# PWR_Supply.net
KiCad netlist of a schematic drawn in Altium Designer
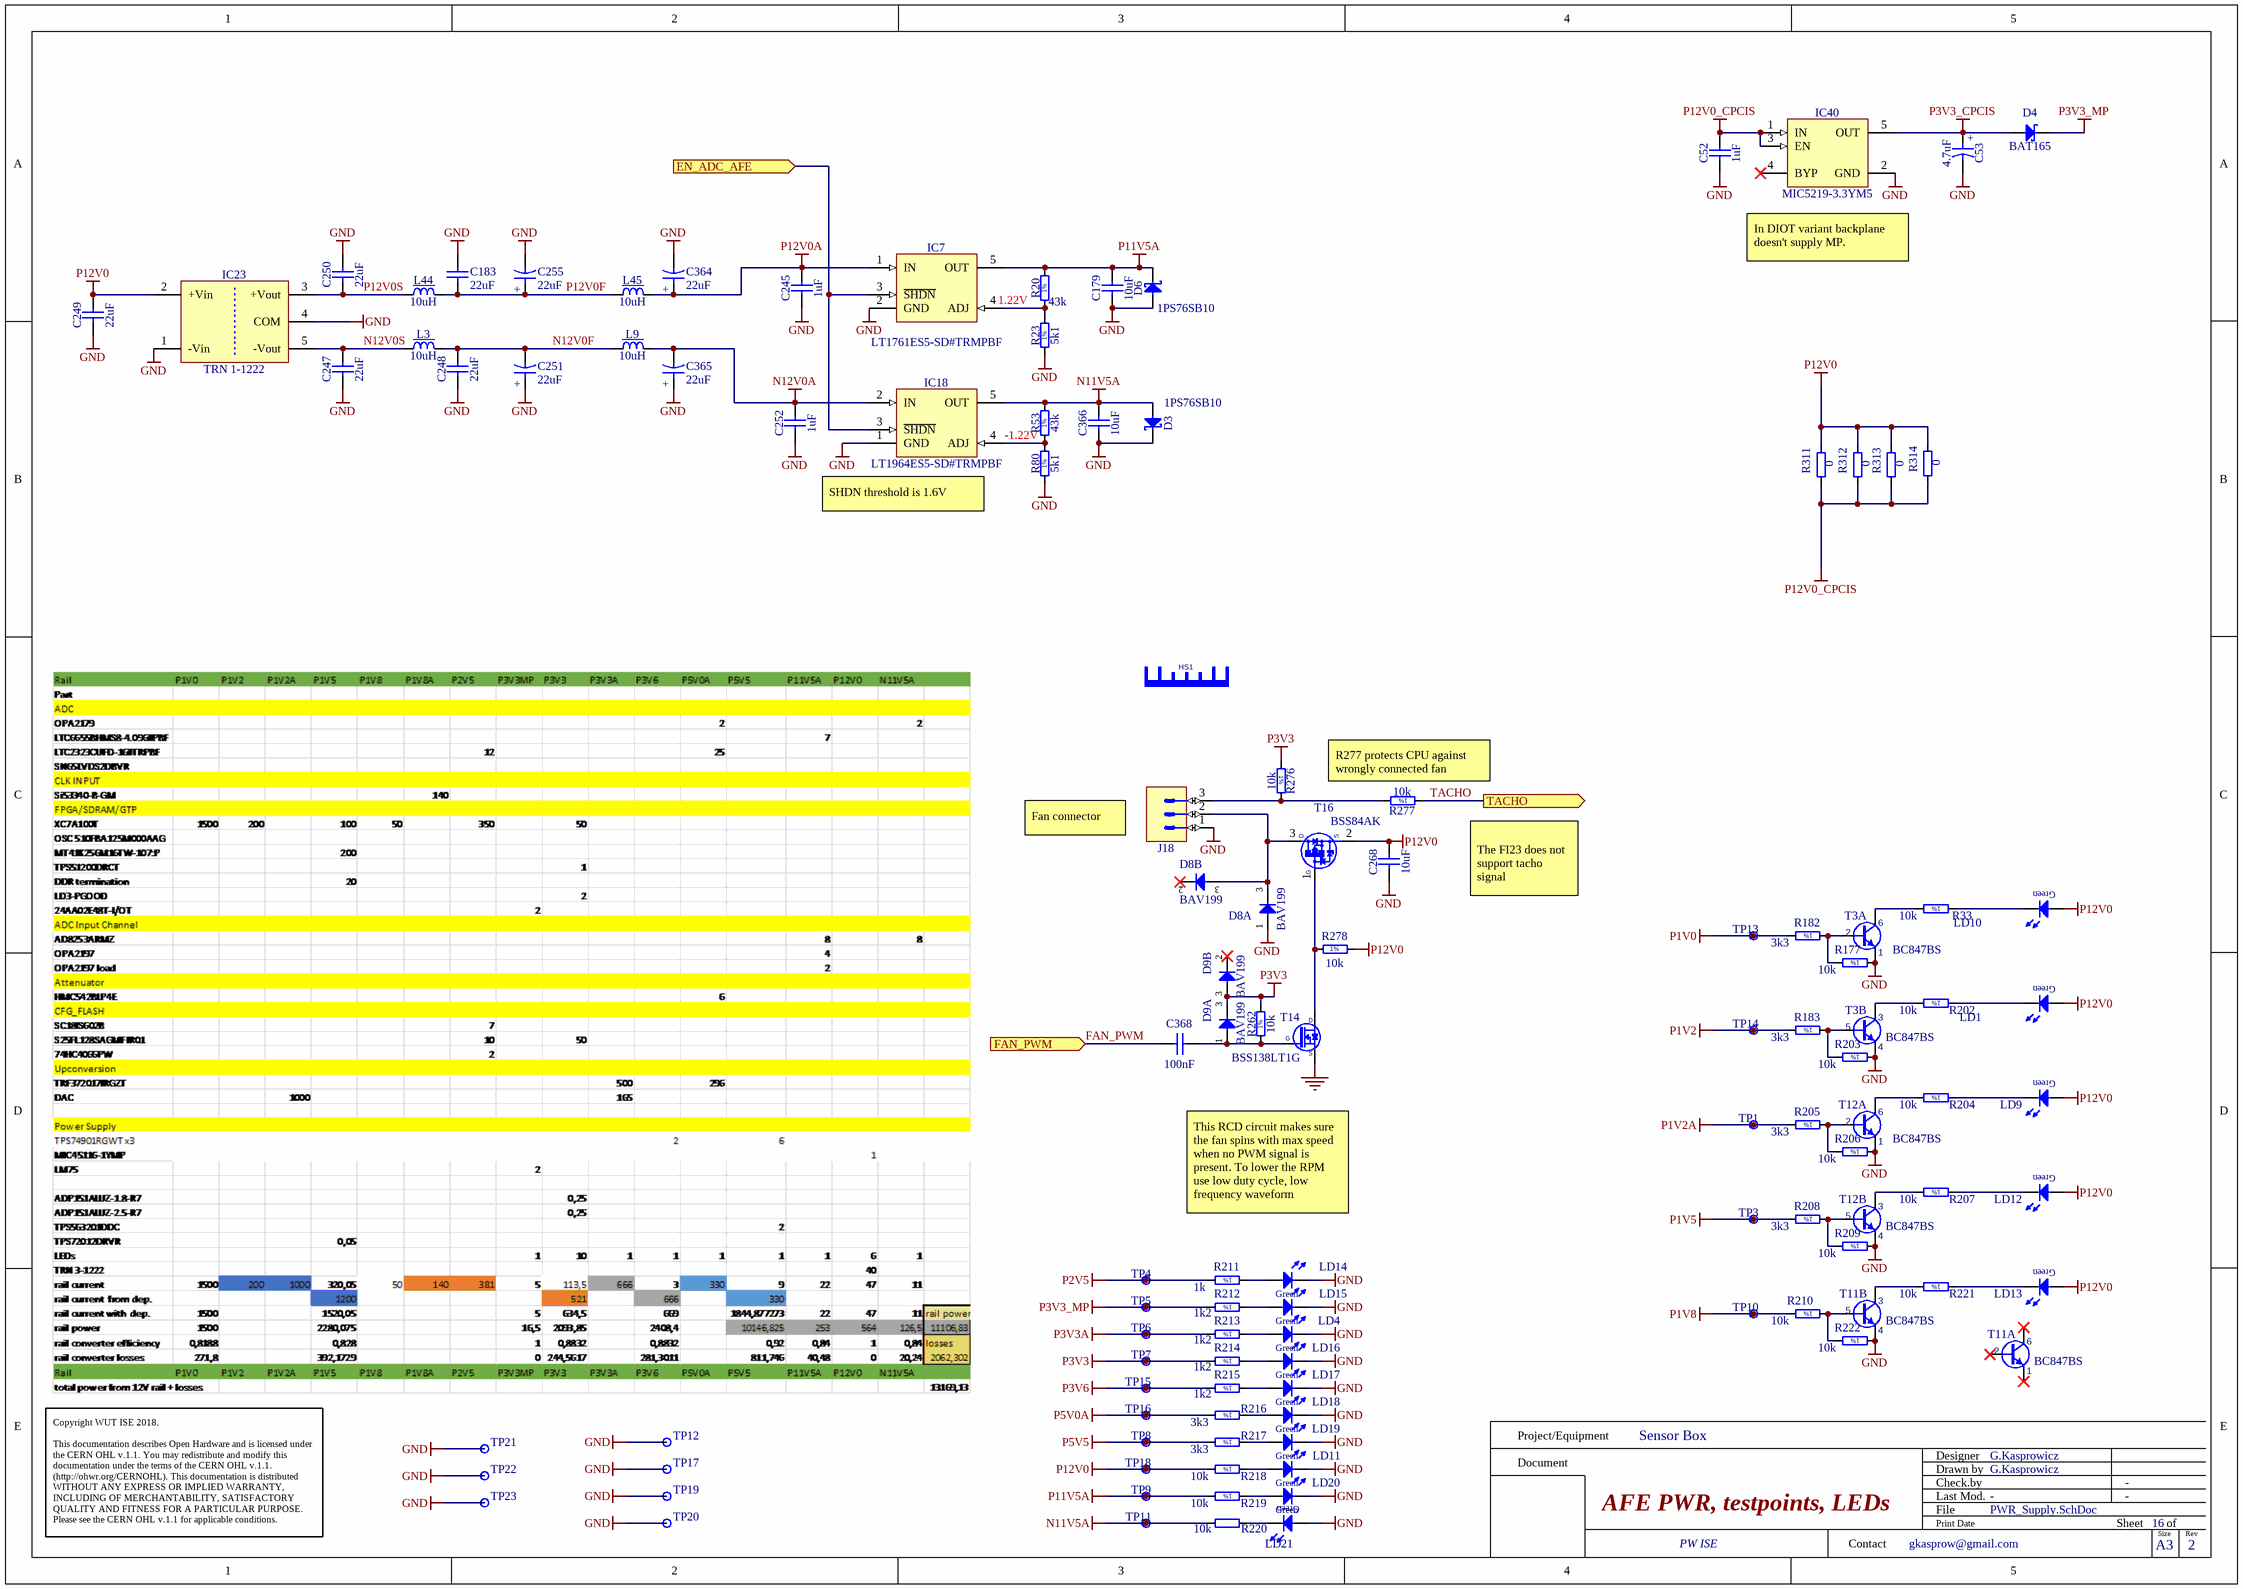
[diagram p0: PWR_Supply.SchDoc]

(export (version "E")
  (design (tool "Eeschema 10.0.6"))
  (components
    (comp (ref "C52")
      (value "1uF")
      (footprint "CAPC1608X87N")
      (description "Non-polarised capacitor")
      (fields (field (name "PART NUMBER") "CC0603_1UF_25V_10%_X7R") (field (name "VOLTAGE") "25V"))
      (libsource (lib "Capacitors") (part "Capacitor - non polarized"))
    )
    (comp (ref "C53")
      (value "4.7uF")
      (footprint "CAPMP3216X180N")
      (description "Polarised capacitor")
      (fields
        (field (name "PART NUMBER") "CTE3216-18_4.7UF_10V_10%_AVX_TPSA475K010T1400")
        (field (name "VOLTAGE") "10V")
      )
      (libsource (lib "Capacitors") (part "Capacitor - polarized"))
    )
    (comp (ref "C179")
      (value "10uF")
      (footprint "CAPC2012X135N")
      (description "Non-polarised capacitor")
      (fields (field (name "PART NUMBER") "CC0805_10UF_16V_10%_X5R") (field (name "VOLTAGE") "16V"))
      (libsource (lib "Capacitors") (part "Capacitor - non polarized"))
    )
    (comp (ref "C183")
      (value "22uF")
      (footprint "CAPC2012X135N")
      (description "Non-polarised capacitor")
      (fields (field (name "PART NUMBER") "CC0805_22UF_16V_10%_X5R") (field (name "VOLTAGE") "16V"))
      (libsource (lib "Capacitors") (part "Capacitor - non polarized"))
    )
    (comp (ref "C245")
      (value "1uF")
      (footprint "CAPC1608X87N")
      (description "Non-polarised capacitor")
      (fields (field (name "PART NUMBER") "CC0603_1UF_25V_10%_X7R") (field (name "VOLTAGE") "25V"))
      (libsource (lib "Capacitors") (part "Capacitor - non polarized"))
    )
    (comp (ref "C247")
      (value "22uF")
      (footprint "CAPC2012X135N")
      (description "Non-polarised capacitor")
      (fields (field (name "PART NUMBER") "CC0805_22UF_16V_10%_X5R") (field (name "VOLTAGE") "16V"))
      (libsource (lib "Capacitors") (part "Capacitor - non polarized"))
    )
    (comp (ref "C248")
      (value "22uF")
      (footprint "CAPC2012X135N")
      (description "Non-polarised capacitor")
      (fields (field (name "PART NUMBER") "CC0805_22UF_16V_10%_X5R") (field (name "VOLTAGE") "16V"))
      (libsource (lib "Capacitors") (part "Capacitor - non polarized"))
    )
    (comp (ref "C249")
      (value "22uF")
      (footprint "CAPC2012X135N")
      (description "Non-polarised capacitor")
      (fields (field (name "PART NUMBER") "CC0805_22UF_16V_10%_X5R") (field (name "VOLTAGE") "16V"))
      (libsource (lib "Capacitors") (part "Capacitor - non polarized"))
    )
    (comp (ref "C250")
      (value "22uF")
      (footprint "CAPC2012X135N")
      (description "Non-polarised capacitor")
      (fields (field (name "PART NUMBER") "CC0805_22UF_16V_10%_X5R") (field (name "VOLTAGE") "16V"))
      (libsource (lib "Capacitors") (part "Capacitor - non polarized"))
    )
    (comp (ref "C251")
      (value "22uF")
      (footprint "CAPMP3528X210N")
      (description "Polarised capacitor")
      (fields (field (name "PART NUMBER") "CTE3528-21_22UF_10V_10%_LESR0700") (field (name "VOLTAGE") "10V"))
      (libsource (lib "Capacitors") (part "Capacitor - polarized"))
    )
    (comp (ref "C252")
      (value "1uF")
      (footprint "CAPC1608X87N")
      (description "Non-polarised capacitor")
      (fields (field (name "PART NUMBER") "CC0603_1UF_25V_10%_X7R") (field (name "VOLTAGE") "25V"))
      (libsource (lib "Capacitors") (part "Capacitor - non polarized"))
    )
    (comp (ref "C255")
      (value "22uF")
      (footprint "CAPMP3528X210N")
      (description "Polarised capacitor")
      (fields (field (name "PART NUMBER") "CTE3528-21_22UF_10V_10%_LESR0700") (field (name "VOLTAGE") "10V"))
      (libsource (lib "Capacitors") (part "Capacitor - polarized"))
    )
    (comp (ref "C268")
      (value "10uF")
      (footprint "CAPC2012X135N")
      (description "Non-polarised capacitor")
      (fields (field (name "PART NUMBER") "CC0805_10UF_16V_10%_X5R") (field (name "VOLTAGE") "16V"))
      (libsource (lib "Capacitors") (part "Capacitor - non polarized"))
    )
    (comp (ref "C364")
      (value "22uF")
      (footprint "CAPMP3528X210N")
      (description "Polarised capacitor")
      (fields (field (name "PART NUMBER") "CTE3528-21_22UF_10V_10%_LESR0700") (field (name "VOLTAGE") "10V"))
      (libsource (lib "Capacitors") (part "Capacitor - polarized"))
    )
    (comp (ref "C365")
      (value "22uF")
      (footprint "CAPMP3528X210N")
      (description "Polarised capacitor")
      (fields (field (name "PART NUMBER") "CTE3528-21_22UF_10V_10%_LESR0700") (field (name "VOLTAGE") "10V"))
      (libsource (lib "Capacitors") (part "Capacitor - polarized"))
    )
    (comp (ref "C366")
      (value "10uF")
      (footprint "CAPC2012X135N")
      (description "Non-polarised capacitor")
      (fields (field (name "PART NUMBER") "CC0805_10UF_16V_10%_X5R") (field (name "VOLTAGE") "16V"))
      (libsource (lib "Capacitors") (part "Capacitor - non polarized"))
    )
    (comp (ref "C368")
      (value "100nF")
      (footprint "CAPC0603X33N")
      (description "Non-polarised capacitor")
      (fields (field (name "PART NUMBER") "CC0201_100NF_6.3V_10%_X5R") (field (name "VOLTAGE") "6.3V"))
      (libsource (lib "Capacitors") (part "Capacitor - non polarized"))
    )
    (comp (ref "D3")
      (value "1PS76SB10")
      (footprint "SOD2512X110N")
      (description "Schottky Diode")
      (fields (field (name "VOLTAGE") "30V") (field (name "POWER") "200mA"))
      (libsource (lib "ICs And Semiconductors") (part "Diode Schottky"))
    )
    (comp (ref "D4")
      (value "BAT165")
      (footprint "SOD2512X110N")
      (description "Schottky Diode")
      (fields (field (name "MANUFACTURER") "INFINEON") (field (name "VOLTAGE") "40V"))
      (libsource (lib "ICs And Semiconductors") (part "Diode Schottky"))
    )
    (comp (ref "D6")
      (value "1PS76SB10")
      (footprint "SOD2512X110N")
      (description "Schottky Diode")
      (fields (field (name "VOLTAGE") "30V") (field (name "POWER") "200mA"))
      (libsource (lib "ICs And Semiconductors") (part "Diode Schottky"))
    )
    (comp (ref "D8")
      (value "BAV199")
      (footprint "SOT95P240X110-3N")
      (description "Serial Diode")
      (fields (field (name "VOLTAGE") "75V") (field (name "POWER") "250mW"))
      (libsource (lib "ICs And Semiconductors") (part "Diode x2 A1C3_A3C2"))
    )
    (comp (ref "D9")
      (value "BAV199")
      (footprint "SOT95P240X110-3N")
      (description "Serial Diode")
      (fields (field (name "VOLTAGE") "75V") (field (name "POWER") "250mW"))
      (libsource (lib "ICs And Semiconductors") (part "Diode x2 A1C3_A3C2"))
    )
    (comp (ref "HS1")
      (value "RADIAN_FI23")
      (footprint "RADIAN_FI23")
      (description "Heat Sink Without Pad")
      (fields
        (field (name "MANUFACTURER") "Radian Thermal Products, Inc.")
        (field (name "MANUFACTURER PART NUMBER") "FI23+BU+T725")
      )
      (libsource (lib "Schlib1") (part "RADIAN_FI23"))
    )
    (comp (ref "IC7")
      (value "LT1761ES5-SD#TRMPBF")
      (footprint "SOT95P280X100-5N")
      (description "100mA, Low Noise, LDO Micropower Adjustable Regulator in SOT-23")
      (fields (field (name "MANUFACTURER") "LINEAR TECHNOLOGY"))
      (libsource (lib "ICs And Semiconductors") (part "LT1761-SD"))
    )
    (comp (ref "IC18")
      (value "LT1964ES5-SD#TRMPBF")
      (footprint "SOT95P280X100-5N")
      (description "200mA, Low Noise, Low Dropout Negative Micropower Regulator")
      (fields (field (name "MANUFACTURER") "LINEAR TECHNOLOGY"))
      (libsource (lib "ICs And Semiconductors") (part "LT1964-SD"))
    )
    (comp (ref "IC23")
      (value "TRN 1-1222")
      (footprint "DCDC_TRACO_TRN1")
      (description "9-18VDC to ±12V, Iout (max) ±45mA, 1W DC-DC Converter")
      (fields (field (name "MANUFACTURER") "TRACO POWER"))
      (libsource (lib "Regulators_SMPS") (part "DCDC_TRACO_TRN 1-1222"))
    )
    (comp (ref "IC40")
      (value "MIC5219-3.3YM5")
      (footprint "SOT95P280X145-5N")
      (description "500mA Peak Output LDO Regulator")
      (fields (field (name "MANUFACTURER") "MICROCHIP TECHNOLOGY"))
      (libsource (lib "ICs And Semiconductors") (part "MIC5219-X.XYM5"))
    )
    (comp (ref "J18")
      (value "KK®")
      (footprint "MOLEX_22-27-2031")
      (description "Connector 3 Male")
      (fields (field (name "PART NUMBER") "MOLEX_22-27-2031") (field (name "MANUFACTURER") "MOLEX"))
      (libsource (lib "Connectors") (part "Connector 3 Male"))
    )
    (comp (ref "L3")
      (value "10uH")
      (footprint "IND_MURATA-PS_8400")
      (description "Inductor With Core")
      (fields (field (name "PART NUMBER") "IND_10UH_10%_MURATA-PS_8400") (field (name "POWER") "950mA"))
      (libsource (lib "Inductors & Transformers") (part "Inductor With Magnetic core"))
    )
    (comp (ref "L9")
      (value "10uH")
      (footprint "IND_MURATA-PS_8400")
      (description "Inductor With Core")
      (fields (field (name "PART NUMBER") "IND_10UH_10%_MURATA-PS_8400") (field (name "POWER") "950mA"))
      (libsource (lib "Inductors & Transformers") (part "Inductor With Magnetic core"))
    )
    (comp (ref "L44")
      (value "10uH")
      (footprint "IND_MURATA-PS_8400")
      (description "Inductor With Core")
      (fields (field (name "PART NUMBER") "IND_10UH_10%_MURATA-PS_8400") (field (name "POWER") "950mA"))
      (libsource (lib "Inductors & Transformers") (part "Inductor With Magnetic core"))
    )
    (comp (ref "L45")
      (value "10uH")
      (footprint "IND_MURATA-PS_8400")
      (description "Inductor With Core")
      (fields (field (name "PART NUMBER") "IND_10UH_10%_MURATA-PS_8400") (field (name "POWER") "950mA"))
      (libsource (lib "Inductors & Transformers") (part "Inductor With Magnetic core"))
    )
    (comp (ref "LD1")
      (value "Green")
      (footprint "LED_KINGBRIGHT_KPH-1608CGCKr")
      (description "Green 0603")
      (fields
        (field (name "PART NUMBER") "LED_KINGBRIGHT_KPH-1608CGCK")
        (field (name "MANUFACTURER") "KINGBRIGHT")
      )
      (libsource (lib "LIBRARY_SCH") (part "LED_0603_Green"))
    )
    (comp (ref "LD4")
      (value "Green")
      (footprint "LED_KINGBRIGHT_KPH-1608CGCKr")
      (description "Green 0603")
      (fields
        (field (name "PART NUMBER") "LED_KINGBRIGHT_KPH-1608CGCK")
        (field (name "MANUFACTURER") "KINGBRIGHT")
      )
      (libsource (lib "LIBRARY_SCH") (part "LED_0603_Green"))
    )
    (comp (ref "LD9")
      (value "Green")
      (footprint "LED_KINGBRIGHT_KPH-1608CGCKr")
      (description "Green 0603")
      (fields
        (field (name "PART NUMBER") "LED_KINGBRIGHT_KPH-1608CGCK")
        (field (name "MANUFACTURER") "KINGBRIGHT")
      )
      (libsource (lib "LIBRARY_SCH") (part "LED_0603_Green"))
    )
    (comp (ref "LD10")
      (value "Green")
      (footprint "LED_KINGBRIGHT_KPH-1608CGCKr")
      (description "Green 0603")
      (fields
        (field (name "PART NUMBER") "LED_KINGBRIGHT_KPH-1608CGCK")
        (field (name "MANUFACTURER") "KINGBRIGHT")
      )
      (libsource (lib "LIBRARY_SCH") (part "LED_0603_Green"))
    )
    (comp (ref "LD11")
      (value "Green")
      (footprint "LED_KINGBRIGHT_KPH-1608CGCKr")
      (description "Green 0603")
      (fields
        (field (name "PART NUMBER") "LED_KINGBRIGHT_KPH-1608CGCK")
        (field (name "MANUFACTURER") "KINGBRIGHT")
      )
      (libsource (lib "LIBRARY_SCH") (part "LED_0603_Green"))
    )
    (comp (ref "LD12")
      (value "Green")
      (footprint "LED_KINGBRIGHT_KPH-1608CGCKr")
      (description "Green 0603")
      (fields
        (field (name "PART NUMBER") "LED_KINGBRIGHT_KPH-1608CGCK")
        (field (name "MANUFACTURER") "KINGBRIGHT")
      )
      (libsource (lib "LIBRARY_SCH") (part "LED_0603_Green"))
    )
    (comp (ref "LD13")
      (value "Green")
      (footprint "LED_KINGBRIGHT_KPH-1608CGCKr")
      (description "Green 0603")
      (fields
        (field (name "PART NUMBER") "LED_KINGBRIGHT_KPH-1608CGCK")
        (field (name "MANUFACTURER") "KINGBRIGHT")
      )
      (libsource (lib "LIBRARY_SCH") (part "LED_0603_Green"))
    )
    (comp (ref "LD14")
      (value "Green")
      (footprint "LED_KINGBRIGHT_KPH-1608CGCKr")
      (description "Green 0603")
      (fields
        (field (name "PART NUMBER") "LED_KINGBRIGHT_KPH-1608CGCK")
        (field (name "MANUFACTURER") "KINGBRIGHT")
      )
      (libsource (lib "LIBRARY_SCH") (part "LED_0603_Green"))
    )
    (comp (ref "LD15")
      (value "Green")
      (footprint "LED_KINGBRIGHT_KPH-1608CGCKr")
      (description "Green 0603")
      (fields
        (field (name "PART NUMBER") "LED_KINGBRIGHT_KPH-1608CGCK")
        (field (name "MANUFACTURER") "KINGBRIGHT")
      )
      (libsource (lib "LIBRARY_SCH") (part "LED_0603_Green"))
    )
    (comp (ref "LD16")
      (value "Green")
      (footprint "LED_KINGBRIGHT_KPH-1608CGCKr")
      (description "Green 0603")
      (fields
        (field (name "PART NUMBER") "LED_KINGBRIGHT_KPH-1608CGCK")
        (field (name "MANUFACTURER") "KINGBRIGHT")
      )
      (libsource (lib "LIBRARY_SCH") (part "LED_0603_Green"))
    )
    (comp (ref "LD17")
      (value "Green")
      (footprint "LED_KINGBRIGHT_KPH-1608CGCKr")
      (description "Green 0603")
      (fields
        (field (name "PART NUMBER") "LED_KINGBRIGHT_KPH-1608CGCK")
        (field (name "MANUFACTURER") "KINGBRIGHT")
      )
      (libsource (lib "LIBRARY_SCH") (part "LED_0603_Green"))
    )
    (comp (ref "LD18")
      (value "Green")
      (footprint "LED_KINGBRIGHT_KPH-1608CGCKr")
      (description "Green 0603")
      (fields
        (field (name "PART NUMBER") "LED_KINGBRIGHT_KPH-1608CGCK")
        (field (name "MANUFACTURER") "KINGBRIGHT")
      )
      (libsource (lib "LIBRARY_SCH") (part "LED_0603_Green"))
    )
    (comp (ref "LD19")
      (value "Green")
      (footprint "LED_KINGBRIGHT_KPH-1608CGCKr")
      (description "Green 0603")
      (fields
        (field (name "PART NUMBER") "LED_KINGBRIGHT_KPH-1608CGCK")
        (field (name "MANUFACTURER") "KINGBRIGHT")
      )
      (libsource (lib "LIBRARY_SCH") (part "LED_0603_Green"))
    )
    (comp (ref "LD20")
      (value "Green")
      (footprint "LED_KINGBRIGHT_KPH-1608CGCKr")
      (description "Green 0603")
      (fields
        (field (name "PART NUMBER") "LED_KINGBRIGHT_KPH-1608CGCK")
        (field (name "MANUFACTURER") "KINGBRIGHT")
      )
      (libsource (lib "LIBRARY_SCH") (part "LED_0603_Green"))
    )
    (comp (ref "LD21")
      (value "Green")
      (footprint "LED_KINGBRIGHT_KPH-1608CGCKr")
      (description "Green 0603")
      (fields
        (field (name "PART NUMBER") "LED_KINGBRIGHT_KPH-1608CGCK")
        (field (name "MANUFACTURER") "KINGBRIGHT")
      )
      (libsource (lib "LIBRARY_SCH") (part "LED_0603_Green"))
    )
    (comp (ref "R20")
      (value "43k")
      (footprint "RESC1005X40N")
      (description "Resistor - 1%")
      (fields (field (name "PART NUMBER") "R0402_43K_1%_0.0625W_100PPM") (field (name "POWER") "0.0625W"))
      (libsource (lib "Resistors") (part "Resistor - 1%"))
    )
    (comp (ref "R23")
      (value "5k1")
      (footprint "RESC1005X40N")
      (description "Resistor - 1%")
      (fields (field (name "PART NUMBER") "R0402_5K1_1%_0.0625W_100PPM") (field (name "POWER") "0.0625W"))
      (libsource (lib "Resistors") (part "Resistor - 1%"))
    )
    (comp (ref "R33")
      (value "10k")
      (footprint "RESC1005X40N")
      (description "Resistor - 1%")
      (fields (field (name "PART NUMBER") "R0402_10K_1%_0.0625W_100PPM") (field (name "POWER") "0.0625W"))
      (libsource (lib "Resistors") (part "Resistor - 1%"))
    )
    (comp (ref "R53")
      (value "43k")
      (footprint "RESC1005X40N")
      (description "Resistor - 1%")
      (fields (field (name "PART NUMBER") "R0402_43K_1%_0.0625W_100PPM") (field (name "POWER") "0.0625W"))
      (libsource (lib "Resistors") (part "Resistor - 1%"))
    )
    (comp (ref "R80")
      (value "5k1")
      (footprint "RESC1005X40N")
      (description "Resistor - 1%")
      (fields (field (name "PART NUMBER") "R0402_5K1_1%_0.0625W_100PPM") (field (name "POWER") "0.0625W"))
      (libsource (lib "Resistors") (part "Resistor - 1%"))
    )
    (comp (ref "R177")
      (value "10k")
      (footprint "RESC1005X40N")
      (description "Resistor - 1%")
      (fields (field (name "PART NUMBER") "R0402_10K_1%_0.0625W_100PPM") (field (name "POWER") "0.0625W"))
      (libsource (lib "Resistors") (part "Resistor - 1%"))
    )
    (comp (ref "R182")
      (value "3k3")
      (footprint "RESC1608X55N")
      (description "Resistor - 1%")
      (fields (field (name "PART NUMBER") "R0603_3K3_1%_0.1W_100PPM") (field (name "POWER") "0.1W"))
      (libsource (lib "Resistors") (part "Resistor - 1%"))
    )
    (comp (ref "R183")
      (value "3k3")
      (footprint "RESC1608X55N")
      (description "Resistor - 1%")
      (fields (field (name "PART NUMBER") "R0603_3K3_1%_0.1W_100PPM") (field (name "POWER") "0.1W"))
      (libsource (lib "Resistors") (part "Resistor - 1%"))
    )
    (comp (ref "R202")
      (value "10k")
      (footprint "RESC1005X40N")
      (description "Resistor - 1%")
      (fields (field (name "PART NUMBER") "R0402_10K_1%_0.0625W_100PPM") (field (name "POWER") "0.0625W"))
      (libsource (lib "Resistors") (part "Resistor - 1%"))
    )
    (comp (ref "R203")
      (value "10k")
      (footprint "RESC1005X40N")
      (description "Resistor - 1%")
      (fields (field (name "PART NUMBER") "R0402_10K_1%_0.0625W_100PPM") (field (name "POWER") "0.0625W"))
      (libsource (lib "Resistors") (part "Resistor - 1%"))
    )
    (comp (ref "R204")
      (value "10k")
      (footprint "RESC1005X40N")
      (description "Resistor - 1%")
      (fields (field (name "PART NUMBER") "R0402_10K_1%_0.0625W_100PPM") (field (name "POWER") "0.0625W"))
      (libsource (lib "Resistors") (part "Resistor - 1%"))
    )
    (comp (ref "R205")
      (value "3k3")
      (footprint "RESC1608X55N")
      (description "Resistor - 1%")
      (fields (field (name "PART NUMBER") "R0603_3K3_1%_0.1W_100PPM") (field (name "POWER") "0.1W"))
      (libsource (lib "Resistors") (part "Resistor - 1%"))
    )
    (comp (ref "R206")
      (value "10k")
      (footprint "RESC1005X40N")
      (description "Resistor - 1%")
      (fields (field (name "PART NUMBER") "R0402_10K_1%_0.0625W_100PPM") (field (name "POWER") "0.0625W"))
      (libsource (lib "Resistors") (part "Resistor - 1%"))
    )
    (comp (ref "R207")
      (value "10k")
      (footprint "RESC1005X40N")
      (description "Resistor - 1%")
      (fields (field (name "PART NUMBER") "R0402_10K_1%_0.0625W_100PPM") (field (name "POWER") "0.0625W"))
      (libsource (lib "Resistors") (part "Resistor - 1%"))
    )
    (comp (ref "R208")
      (value "3k3")
      (footprint "RESC1608X55N")
      (description "Resistor - 1%")
      (fields (field (name "PART NUMBER") "R0603_3K3_1%_0.1W_100PPM") (field (name "POWER") "0.1W"))
      (libsource (lib "Resistors") (part "Resistor - 1%"))
    )
    (comp (ref "R209")
      (value "10k")
      (footprint "RESC1005X40N")
      (description "Resistor - 1%")
      (fields (field (name "PART NUMBER") "R0402_10K_1%_0.0625W_100PPM") (field (name "POWER") "0.0625W"))
      (libsource (lib "Resistors") (part "Resistor - 1%"))
    )
    (comp (ref "R210")
      (value "10k")
      (footprint "RESC1005X40N")
      (description "Resistor - 1%")
      (fields (field (name "PART NUMBER") "R0402_10K_1%_0.0625W_100PPM") (field (name "POWER") "0.0625W"))
      (libsource (lib "Resistors") (part "Resistor - 1%"))
    )
    (comp (ref "R211")
      (value "1k")
      (footprint "RESC1608X55N")
      (description "Resistor - 1%")
      (fields (field (name "PART NUMBER") "R0603_1K_1%_0.1W_100PPM") (field (name "POWER") "0.1W"))
      (libsource (lib "Resistors") (part "Resistor - 1%"))
    )
    (comp (ref "R212")
      (value "1k2")
      (footprint "RESC1608X55N")
      (description "Resistor - 1%")
      (fields (field (name "PART NUMBER") "R0603_1K2_1%_0.1W_100PPM") (field (name "POWER") "0.1W"))
      (libsource (lib "Resistors") (part "Resistor - 1%"))
    )
    (comp (ref "R213")
      (value "1k2")
      (footprint "RESC1608X55N")
      (description "Resistor - 1%")
      (fields (field (name "PART NUMBER") "R0603_1K2_1%_0.1W_100PPM") (field (name "POWER") "0.1W"))
      (libsource (lib "Resistors") (part "Resistor - 1%"))
    )
    (comp (ref "R214")
      (value "1k2")
      (footprint "RESC1608X55N")
      (description "Resistor - 1%")
      (fields (field (name "PART NUMBER") "R0603_1K2_1%_0.1W_100PPM") (field (name "POWER") "0.1W"))
      (libsource (lib "Resistors") (part "Resistor - 1%"))
    )
    (comp (ref "R215")
      (value "1k2")
      (footprint "RESC1608X55N")
      (description "Resistor - 1%")
      (fields (field (name "PART NUMBER") "R0603_1K2_1%_0.1W_100PPM") (field (name "POWER") "0.1W"))
      (libsource (lib "Resistors") (part "Resistor - 1%"))
    )
    (comp (ref "R216")
      (value "3k3")
      (footprint "RESC1608X55N")
      (description "Resistor - 1%")
      (fields (field (name "PART NUMBER") "R0603_3K3_1%_0.1W_100PPM") (field (name "POWER") "0.1W"))
      (libsource (lib "Resistors") (part "Resistor - 1%"))
    )
    (comp (ref "R217")
      (value "3k3")
      (footprint "RESC1608X55N")
      (description "Resistor - 1%")
      (fields (field (name "PART NUMBER") "R0603_3K3_1%_0.1W_100PPM") (field (name "POWER") "0.1W"))
      (libsource (lib "Resistors") (part "Resistor - 1%"))
    )
    (comp (ref "R218")
      (value "10k")
      (footprint "RESC1005X40N")
      (description "Resistor - 1%")
      (fields (field (name "PART NUMBER") "R0402_10K_1%_0.0625W_100PPM") (field (name "POWER") "0.0625W"))
      (libsource (lib "Resistors") (part "Resistor - 1%"))
    )
    (comp (ref "R219")
      (value "10k")
      (footprint "RESC1005X40N")
      (description "Resistor - 1%")
      (fields (field (name "PART NUMBER") "R0402_10K_1%_0.0625W_100PPM") (field (name "POWER") "0.0625W"))
      (libsource (lib "Resistors") (part "Resistor - 1%"))
    )
    (comp (ref "R220")
      (value "10k")
      (footprint "RESC1608X55N")
      (description "Resistor - 1%")
      (fields (field (name "PART NUMBER") "R0603_10K_1%_0.1W_100PPM") (field (name "POWER") "0.1W"))
      (libsource (lib "") (part "Resistor - 1%_1"))
    )
    (comp (ref "R221")
      (value "10k")
      (footprint "RESC1005X40N")
      (description "Resistor - 1%")
      (fields (field (name "PART NUMBER") "R0402_10K_1%_0.0625W_100PPM") (field (name "POWER") "0.0625W"))
      (libsource (lib "Resistors") (part "Resistor - 1%"))
    )
    (comp (ref "R222")
      (value "10k")
      (footprint "RESC1005X40N")
      (description "Resistor - 1%")
      (fields (field (name "PART NUMBER") "R0402_10K_1%_0.0625W_100PPM") (field (name "POWER") "0.0625W"))
      (libsource (lib "Resistors") (part "Resistor - 1%"))
    )
    (comp (ref "R262")
      (value "10k")
      (footprint "RESC1005X40N")
      (description "Resistor - 1%")
      (fields (field (name "PART NUMBER") "R0402_10K_1%_0.0625W_100PPM") (field (name "POWER") "0.0625W"))
      (libsource (lib "Resistors") (part "Resistor - 1%"))
    )
    (comp (ref "R276")
      (value "10k")
      (footprint "RESC1005X40N")
      (description "Resistor - 1%")
      (fields (field (name "PART NUMBER") "R0402_10K_1%_0.0625W_100PPM") (field (name "POWER") "0.0625W"))
      (libsource (lib "Resistors") (part "Resistor - 1%"))
    )
    (comp (ref "R277")
      (value "10k")
      (footprint "RESC1005X40N")
      (description "Resistor - 1%")
      (fields (field (name "PART NUMBER") "R0402_10K_1%_0.0625W_100PPM") (field (name "POWER") "0.0625W"))
      (libsource (lib "Resistors") (part "Resistor - 1%"))
    )
    (comp (ref "R278")
      (value "10k")
      (footprint "RESC1005X40N")
      (description "Resistor - 1%")
      (fields (field (name "PART NUMBER") "R0402_10K_1%_0.0625W_100PPM") (field (name "POWER") "0.0625W"))
      (libsource (lib "Resistors") (part "Resistor - 1%"))
    )
    (comp (ref "R311")
      (value "0")
      (footprint "RESC1005X35N")
      (description "Resistor")
      (fields (field (name "PART NUMBER") "R0603_0R_JUMPER") (field (name "MANUFACTURER") "GENERIC"))
      (libsource (lib "Resistors") (part "Resistor"))
    )
    (comp (ref "R312")
      (value "0")
      (footprint "RESC1005X35N")
      (description "Resistor")
      (fields (field (name "PART NUMBER") "R0603_0R_JUMPER") (field (name "MANUFACTURER") "GENERIC"))
      (libsource (lib "Resistors") (part "Resistor"))
    )
    (comp (ref "R313")
      (value "0")
      (footprint "RESC1005X35N")
      (description "Resistor")
      (fields (field (name "PART NUMBER") "R0603_0R_JUMPER") (field (name "MANUFACTURER") "GENERIC"))
      (libsource (lib "Resistors") (part "Resistor"))
    )
    (comp (ref "R314")
      (value "0")
      (footprint "RESC1005X35N")
      (description "Resistor")
      (fields (field (name "PART NUMBER") "R0603_0R_JUMPER") (field (name "MANUFACTURER") "GENERIC"))
      (libsource (lib "Resistors") (part "Resistor"))
    )
    (comp (ref "T3")
      (value "BC847BS")
      (footprint "SOT65P210X110-6N")
      (description "45V 100mA Dual NPN General-Purpose Transistor")
      (fields (field (name "MANUFACTURER") "NXP SEMICONDUCTORS"))
      (libsource (lib "ICs And Semiconductors") (part "BC847BS"))
    )
    (comp (ref "T11")
      (value "BC847BS")
      (footprint "SOT65P210X110-6N")
      (description "45V 100mA Dual NPN General-Purpose Transistor")
      (fields (field (name "MANUFACTURER") "NXP SEMICONDUCTORS"))
      (libsource (lib "ICs And Semiconductors") (part "BC847BS"))
    )
    (comp (ref "T12")
      (value "BC847BS")
      (footprint "SOT65P210X110-6N")
      (description "45V 100mA Dual NPN General-Purpose Transistor")
      (fields (field (name "MANUFACTURER") "NXP SEMICONDUCTORS"))
      (libsource (lib "ICs And Semiconductors") (part "BC847BS"))
    )
    (comp (ref "T14")
      (value "BSS138LT1G")
      (footprint "SOT95P240X110-3N")
      (description "N-CHANNEL MOSFET WITH DIODE")
      (fields (field (name "MANUFACTURER") "ON SEMICONDUCTOR"))
      (libsource (lib "ICs And Semiconductors") (part "N-MOSFET-D 1G 2S 3D"))
    )
    (comp (ref "T16")
      (value "BSS84AK")
      (footprint "SOT95P230X110-3N")
      (description "50V, 180mA P-Channel Trench MOSFET")
      (fields (field (name "MANUFACTURER") "NXP SEMICONDUCTORS"))
      (libsource (lib "ICs And Semiconductors") (part "BSS84"))
    )
    (comp (ref "TP1")
      (value "Test Point")
      (footprint "TPS127")
      (fields (field (name "PART NUMBER") "SMD_PAD_1.27X1.27MM"))
      (libsource (lib "Eletro-mechanical") (part "Test Point"))
    )
    (comp (ref "TP3")
      (value "Test Point")
      (footprint "TPS127")
      (fields (field (name "PART NUMBER") "SMD_PAD_1.27X1.27MM"))
      (libsource (lib "Eletro-mechanical") (part "Test Point"))
    )
    (comp (ref "TP4")
      (value "Test Point")
      (footprint "TPS127")
      (fields (field (name "PART NUMBER") "SMD_PAD_1.27X1.27MM"))
      (libsource (lib "Eletro-mechanical") (part "Test Point"))
    )
    (comp (ref "TP5")
      (value "Test Point")
      (footprint "TPS127")
      (fields (field (name "PART NUMBER") "SMD_PAD_1.27X1.27MM"))
      (libsource (lib "Eletro-mechanical") (part "Test Point"))
    )
    (comp (ref "TP6")
      (value "Test Point")
      (footprint "TPS127")
      (fields (field (name "PART NUMBER") "SMD_PAD_1.27X1.27MM"))
      (libsource (lib "Eletro-mechanical") (part "Test Point"))
    )
    (comp (ref "TP7")
      (value "Test Point")
      (footprint "TPS127")
      (fields (field (name "PART NUMBER") "SMD_PAD_1.27X1.27MM"))
      (libsource (lib "Eletro-mechanical") (part "Test Point"))
    )
    (comp (ref "TP8")
      (value "Test Point")
      (footprint "TPS127")
      (fields (field (name "PART NUMBER") "SMD_PAD_1.27X1.27MM"))
      (libsource (lib "Eletro-mechanical") (part "Test Point"))
    )
    (comp (ref "TP9")
      (value "Test Point")
      (footprint "TPS127")
      (fields (field (name "PART NUMBER") "SMD_PAD_1.27X1.27MM"))
      (libsource (lib "Eletro-mechanical") (part "Test Point"))
    )
    (comp (ref "TP10")
      (value "Test Point")
      (footprint "TPS127")
      (fields (field (name "PART NUMBER") "SMD_PAD_1.27X1.27MM"))
      (libsource (lib "Eletro-mechanical") (part "Test Point"))
    )
    (comp (ref "TP11")
      (value "Test Point")
      (footprint "TPS127")
      (fields (field (name "PART NUMBER") "SMD_PAD_1.27X1.27MM"))
      (libsource (lib "Eletro-mechanical") (part "Test Point"))
    )
    (comp (ref "TP12")
      (value "Test Point")
      (footprint "TPS127")
      (fields (field (name "PART NUMBER") "SMD_PAD_1.27X1.27MM"))
      (libsource (lib "Eletro-mechanical") (part "Test Point"))
    )
    (comp (ref "TP13")
      (value "Test Point")
      (footprint "TPS127")
      (fields (field (name "PART NUMBER") "SMD_PAD_1.27X1.27MM"))
      (libsource (lib "Eletro-mechanical") (part "Test Point"))
    )
    (comp (ref "TP14")
      (value "Test Point")
      (footprint "TPS127")
      (fields (field (name "PART NUMBER") "SMD_PAD_1.27X1.27MM"))
      (libsource (lib "Eletro-mechanical") (part "Test Point"))
    )
    (comp (ref "TP15")
      (value "Test Point")
      (footprint "TPS127")
      (fields (field (name "PART NUMBER") "SMD_PAD_1.27X1.27MM"))
      (libsource (lib "Eletro-mechanical") (part "Test Point"))
    )
    (comp (ref "TP16")
      (value "Test Point")
      (footprint "TPS127")
      (fields (field (name "PART NUMBER") "SMD_PAD_1.27X1.27MM"))
      (libsource (lib "Eletro-mechanical") (part "Test Point"))
    )
    (comp (ref "TP17")
      (value "Test Point")
      (footprint "TPS127")
      (fields (field (name "PART NUMBER") "SMD_PAD_1.27X1.27MM"))
      (libsource (lib "Eletro-mechanical") (part "Test Point"))
    )
    (comp (ref "TP18")
      (value "Test Point")
      (footprint "TPS127")
      (fields (field (name "PART NUMBER") "SMD_PAD_1.27X1.27MM"))
      (libsource (lib "Eletro-mechanical") (part "Test Point"))
    )
    (comp (ref "TP19")
      (value "Test Point")
      (footprint "TPS127")
      (fields (field (name "PART NUMBER") "SMD_PAD_1.27X1.27MM"))
      (libsource (lib "Eletro-mechanical") (part "Test Point"))
    )
    (comp (ref "TP20")
      (value "Test Point")
      (footprint "TPS127")
      (fields (field (name "PART NUMBER") "SMD_PAD_1.27X1.27MM"))
      (libsource (lib "Eletro-mechanical") (part "Test Point"))
    )
    (comp (ref "TP21")
      (value "Test Point")
      (footprint "TPS127")
      (fields (field (name "PART NUMBER") "SMD_PAD_1.27X1.27MM"))
      (libsource (lib "Eletro-mechanical") (part "Test Point"))
    )
    (comp (ref "TP22")
      (value "Test Point")
      (footprint "TPS127")
      (fields (field (name "PART NUMBER") "SMD_PAD_1.27X1.27MM"))
      (libsource (lib "Eletro-mechanical") (part "Test Point"))
    )
    (comp (ref "TP23")
      (value "Test Point")
      (footprint "TPS127")
      (fields (field (name "PART NUMBER") "SMD_PAD_1.27X1.27MM"))
      (libsource (lib "Eletro-mechanical") (part "Test Point"))
    )
  )
  (nets
    (net (code "1") (name "/EN_ADC_AFE") (class "Default")
      (node (ref "IC18") (pin "3") (pinfunction "~{SHDN}_3") (pintype "input"))
      (node (ref "IC7") (pin "3") (pinfunction "~{SHDN}_3") (pintype "input"))
    )
    (net (code "2") (name "/FAN_PWM") (class "Default")
      (node (ref "C368") (pin "2") (pinfunction "2_2") (pintype "passive"))
    )
    (net (code "3") (name "/N12V0F") (class "Default")
      (node (ref "C248") (pin "2") (pinfunction "2_2") (pintype "passive"))
      (node (ref "C251") (pin "2") (pinfunction "2_2") (pintype "passive"))
      (node (ref "L3") (pin "2") (pinfunction "2_2") (pintype "passive"))
      (node (ref "L9") (pin "1") (pinfunction "1_1") (pintype "passive"))
    )
    (net (code "4") (name "/N12V0S") (class "Default")
      (node (ref "C247") (pin "2") (pinfunction "2_2") (pintype "passive"))
      (node (ref "IC23") (pin "5") (pinfunction "-Vout_5") (pintype "power_in"))
      (node (ref "L3") (pin "1") (pinfunction "1_1") (pintype "passive"))
    )
    (net (code "5") (name "/P12V0F") (class "Default")
      (node (ref "C183") (pin "2") (pinfunction "2_2") (pintype "passive"))
      (node (ref "C255") (pin "1") (pinfunction "1_1") (pintype "passive"))
      (node (ref "L44") (pin "2") (pinfunction "2_2") (pintype "passive"))
      (node (ref "L45") (pin "1") (pinfunction "1_1") (pintype "passive"))
    )
    (net (code "6") (name "/P12V0S") (class "Default")
      (node (ref "C250") (pin "1") (pinfunction "1_1") (pintype "passive"))
      (node (ref "IC23") (pin "3") (pinfunction "+Vout_3") (pintype "power_in"))
      (node (ref "L44") (pin "1") (pinfunction "1_1") (pintype "passive"))
    )
    (net (code "7") (name "/TACHO") (class "Default")
      (node (ref "R277") (pin "1") (pinfunction "1_1") (pintype "passive"))
    )
    (net (code "8") (name "GND") (class "Default")
      (node (ref "C179") (pin "1") (pinfunction "1_1") (pintype "passive"))
      (node (ref "C183") (pin "1") (pinfunction "1_1") (pintype "passive"))
      (node (ref "C245") (pin "1") (pinfunction "1_1") (pintype "passive"))
      (node (ref "C247") (pin "1") (pinfunction "1_1") (pintype "passive"))
      (node (ref "C248") (pin "1") (pinfunction "1_1") (pintype "passive"))
      (node (ref "C249") (pin "1") (pinfunction "1_1") (pintype "passive"))
      (node (ref "C250") (pin "2") (pinfunction "2_2") (pintype "passive"))
      (node (ref "C251") (pin "1") (pinfunction "1_1") (pintype "passive"))
      (node (ref "C252") (pin "1") (pinfunction "1_1") (pintype "passive"))
      (node (ref "C255") (pin "2") (pinfunction "2_2") (pintype "passive"))
      (node (ref "C268") (pin "1") (pinfunction "1_1") (pintype "passive"))
      (node (ref "C364") (pin "2") (pinfunction "2_2") (pintype "passive"))
      (node (ref "C365") (pin "1") (pinfunction "1_1") (pintype "passive"))
      (node (ref "C366") (pin "1") (pinfunction "1_1") (pintype "passive"))
      (node (ref "C52") (pin "1") (pinfunction "1_1") (pintype "passive"))
      (node (ref "C53") (pin "2") (pinfunction "2_2") (pintype "passive"))
      (node (ref "D3") (pin "1") (pinfunction "C_1") (pintype "passive"))
      (node (ref "D6") (pin "2") (pinfunction "A_2") (pintype "passive"))
      (node (ref "D8") (pin "1") (pinfunction "A_1") (pintype "passive"))
      (node (ref "IC18") (pin "1") (pinfunction "GND_1") (pintype "power_in"))
      (node (ref "IC23") (pin "1") (pinfunction "-Vin_1") (pintype "power_in"))
      (node (ref "IC23") (pin "4") (pinfunction "COM_4") (pintype "power_in"))
      (node (ref "IC40") (pin "2") (pinfunction "GND_2") (pintype "power_in"))
      (node (ref "IC7") (pin "2") (pinfunction "GND_2") (pintype "power_in"))
      (node (ref "J18") (pin "1") (pinfunction "1_1") (pintype "bidirectional"))
      (node (ref "LD11") (pin "1") (pinfunction "C_1") (pintype "passive"))
      (node (ref "LD14") (pin "1") (pinfunction "C_1") (pintype "passive"))
      (node (ref "LD15") (pin "1") (pinfunction "C_1") (pintype "passive"))
      (node (ref "LD16") (pin "1") (pinfunction "C_1") (pintype "passive"))
      (node (ref "LD17") (pin "1") (pinfunction "C_1") (pintype "passive"))
      (node (ref "LD18") (pin "1") (pinfunction "C_1") (pintype "passive"))
      (node (ref "LD19") (pin "1") (pinfunction "C_1") (pintype "passive"))
      (node (ref "LD20") (pin "1") (pinfunction "C_1") (pintype "passive"))
      (node (ref "LD21") (pin "2") (pinfunction "A_2") (pintype "passive"))
      (node (ref "LD4") (pin "1") (pinfunction "C_1") (pintype "passive"))
      (node (ref "R177") (pin "1") (pinfunction "1_1") (pintype "passive"))
      (node (ref "R203") (pin "1") (pinfunction "1_1") (pintype "passive"))
      (node (ref "R206") (pin "1") (pinfunction "1_1") (pintype "passive"))
      (node (ref "R209") (pin "1") (pinfunction "1_1") (pintype "passive"))
      (node (ref "R222") (pin "1") (pinfunction "1_1") (pintype "passive"))
      (node (ref "R23") (pin "1") (pinfunction "1_1") (pintype "passive"))
      (node (ref "R80") (pin "1") (pinfunction "1_1") (pintype "passive"))
      (node (ref "T11") (pin "4") (pinfunction "E_4") (pintype "passive"))
      (node (ref "T12") (pin "1") (pinfunction "E_1") (pintype "passive"))
      (node (ref "T12") (pin "4") (pinfunction "E_4") (pintype "passive"))
      (node (ref "T14") (pin "2") (pinfunction "S_2") (pintype "passive"))
      (node (ref "T3") (pin "1") (pinfunction "E_1") (pintype "passive"))
      (node (ref "T3") (pin "4") (pinfunction "E_4") (pintype "passive"))
      (node (ref "TP12") (pin "1") (pinfunction "1_1") (pintype "bidirectional"))
      (node (ref "TP17") (pin "1") (pinfunction "1_1") (pintype "bidirectional"))
      (node (ref "TP19") (pin "1") (pinfunction "1_1") (pintype "bidirectional"))
      (node (ref "TP20") (pin "1") (pinfunction "1_1") (pintype "bidirectional"))
      (node (ref "TP21") (pin "1") (pinfunction "1_1") (pintype "bidirectional"))
      (node (ref "TP22") (pin "1") (pinfunction "1_1") (pintype "bidirectional"))
      (node (ref "TP23") (pin "1") (pinfunction "1_1") (pintype "bidirectional"))
    )
    (net (code "9") (name "N11V5A") (class "Default")
      (node (ref "C366") (pin "2") (pinfunction "2_2") (pintype "passive"))
      (node (ref "D3") (pin "2") (pinfunction "A_2") (pintype "passive"))
      (node (ref "IC18") (pin "5") (pinfunction "OUT_5") (pintype "power_in"))
      (node (ref "R220") (pin "2") (pinfunction "2_2") (pintype "passive"))
      (node (ref "R53") (pin "2") (pinfunction "2_2") (pintype "passive"))
      (node (ref "TP11") (pin "1") (pinfunction "1_1") (pintype "bidirectional"))
    )
    (net (code "10") (name "N12V0A") (class "Default")
      (node (ref "C252") (pin "2") (pinfunction "2_2") (pintype "passive"))
      (node (ref "C365") (pin "2") (pinfunction "2_2") (pintype "passive"))
      (node (ref "IC18") (pin "2") (pinfunction "IN_2") (pintype "input"))
      (node (ref "L9") (pin "2") (pinfunction "2_2") (pintype "passive"))
    )
    (net (code "11") (name "Net-(D8A-COMAC)") (class "Default")
      (node (ref "D8") (pin "3") (pinfunction "COMAC_3") (pintype "passive"))
      (node (ref "J18") (pin "2") (pinfunction "2_2") (pintype "bidirectional"))
      (node (ref "T16") (pin "3") (pinfunction "D_3") (pintype "passive"))
    )
    (net (code "12") (name "Net-(D9A-A)") (class "Default")
      (node (ref "C368") (pin "1") (pinfunction "1_1") (pintype "passive"))
      (node (ref "D9") (pin "1") (pinfunction "A_1") (pintype "passive"))
      (node (ref "R262") (pin "1") (pinfunction "1_1") (pintype "passive"))
      (node (ref "T14") (pin "1") (pinfunction "G_1") (pintype "passive"))
    )
    (net (code "13") (name "Net-(IC7-ADJ)") (class "Default")
      (node (ref "IC7") (pin "4") (pinfunction "ADJ_4") (pintype "input"))
      (node (ref "R20") (pin "1") (pinfunction "1_1") (pintype "passive"))
      (node (ref "R23") (pin "2") (pinfunction "2_2") (pintype "passive"))
    )
    (net (code "14") (name "Net-(IC18-ADJ)") (class "Default")
      (node (ref "IC18") (pin "4") (pinfunction "ADJ_4") (pintype "input"))
      (node (ref "R53") (pin "1") (pinfunction "1_1") (pintype "passive"))
      (node (ref "R80") (pin "2") (pinfunction "2_2") (pintype "passive"))
    )
    (net (code "15") (name "Net-(J18-Pad3)") (class "Default")
      (node (ref "J18") (pin "3") (pinfunction "3_3") (pintype "bidirectional"))
      (node (ref "R276") (pin "2") (pinfunction "2_2") (pintype "passive"))
      (node (ref "R277") (pin "2") (pinfunction "2_2") (pintype "passive"))
    )
    (net (code "16") (name "Net-(LD1-C)") (class "Default")
      (node (ref "LD1") (pin "1") (pinfunction "C_1") (pintype "passive"))
      (node (ref "R202") (pin "1") (pinfunction "1_1") (pintype "passive"))
    )
    (net (code "17") (name "Net-(LD4-A)") (class "Default")
      (node (ref "LD4") (pin "2") (pinfunction "A_2") (pintype "passive"))
      (node (ref "R213") (pin "1") (pinfunction "1_1") (pintype "passive"))
    )
    (net (code "18") (name "Net-(LD9-C)") (class "Default")
      (node (ref "LD9") (pin "1") (pinfunction "C_1") (pintype "passive"))
      (node (ref "R204") (pin "1") (pinfunction "1_1") (pintype "passive"))
    )
    (net (code "19") (name "Net-(LD10-C)") (class "Default")
      (node (ref "LD10") (pin "1") (pinfunction "C_1") (pintype "passive"))
      (node (ref "R33") (pin "1") (pinfunction "1_1") (pintype "passive"))
    )
    (net (code "20") (name "Net-(LD11-A)") (class "Default")
      (node (ref "LD11") (pin "2") (pinfunction "A_2") (pintype "passive"))
      (node (ref "R218") (pin "1") (pinfunction "1_1") (pintype "passive"))
    )
    (net (code "21") (name "Net-(LD12-C)") (class "Default")
      (node (ref "LD12") (pin "1") (pinfunction "C_1") (pintype "passive"))
      (node (ref "R207") (pin "1") (pinfunction "1_1") (pintype "passive"))
    )
    (net (code "22") (name "Net-(LD13-C)") (class "Default")
      (node (ref "LD13") (pin "1") (pinfunction "C_1") (pintype "passive"))
      (node (ref "R221") (pin "1") (pinfunction "1_1") (pintype "passive"))
    )
    (net (code "23") (name "Net-(LD14-A)") (class "Default")
      (node (ref "LD14") (pin "2") (pinfunction "A_2") (pintype "passive"))
      (node (ref "R211") (pin "1") (pinfunction "1_1") (pintype "passive"))
    )
    (net (code "24") (name "Net-(LD15-A)") (class "Default")
      (node (ref "LD15") (pin "2") (pinfunction "A_2") (pintype "passive"))
      (node (ref "R212") (pin "1") (pinfunction "1_1") (pintype "passive"))
    )
    (net (code "25") (name "Net-(LD16-A)") (class "Default")
      (node (ref "LD16") (pin "2") (pinfunction "A_2") (pintype "passive"))
      (node (ref "R214") (pin "1") (pinfunction "1_1") (pintype "passive"))
    )
    (net (code "26") (name "Net-(LD17-A)") (class "Default")
      (node (ref "LD17") (pin "2") (pinfunction "A_2") (pintype "passive"))
      (node (ref "R215") (pin "1") (pinfunction "1_1") (pintype "passive"))
    )
    (net (code "27") (name "Net-(LD18-A)") (class "Default")
      (node (ref "LD18") (pin "2") (pinfunction "A_2") (pintype "passive"))
      (node (ref "R216") (pin "1") (pinfunction "1_1") (pintype "passive"))
    )
    (net (code "28") (name "Net-(LD19-A)") (class "Default")
      (node (ref "LD19") (pin "2") (pinfunction "A_2") (pintype "passive"))
      (node (ref "R217") (pin "1") (pinfunction "1_1") (pintype "passive"))
    )
    (net (code "29") (name "Net-(LD20-A)") (class "Default")
      (node (ref "LD20") (pin "2") (pinfunction "A_2") (pintype "passive"))
      (node (ref "R219") (pin "1") (pinfunction "1_1") (pintype "passive"))
    )
    (net (code "30") (name "Net-(LD21-C)") (class "Default")
      (node (ref "LD21") (pin "1") (pinfunction "C_1") (pintype "passive"))
      (node (ref "R220") (pin "1") (pinfunction "1_1") (pintype "passive"))
    )
    (net (code "31") (name "Net-(T3A-B)") (class "Default")
      (node (ref "R177") (pin "2") (pinfunction "2_2") (pintype "passive"))
      (node (ref "R182") (pin "1") (pinfunction "1_1") (pintype "passive"))
      (node (ref "T3") (pin "2") (pinfunction "B_2") (pintype "passive"))
    )
    (net (code "32") (name "Net-(T3A-C)") (class "Default")
      (node (ref "R33") (pin "2") (pinfunction "2_2") (pintype "passive"))
      (node (ref "T3") (pin "6") (pinfunction "C_6") (pintype "passive"))
    )
    (net (code "33") (name "Net-(T3B-B)") (class "Default")
      (node (ref "R183") (pin "1") (pinfunction "1_1") (pintype "passive"))
      (node (ref "R203") (pin "2") (pinfunction "2_2") (pintype "passive"))
      (node (ref "T3") (pin "5") (pinfunction "B_5") (pintype "passive"))
    )
    (net (code "34") (name "Net-(T3B-C)") (class "Default")
      (node (ref "R202") (pin "2") (pinfunction "2_2") (pintype "passive"))
      (node (ref "T3") (pin "3") (pinfunction "C_3") (pintype "passive"))
    )
    (net (code "35") (name "Net-(T11B-B)") (class "Default")
      (node (ref "R210") (pin "1") (pinfunction "1_1") (pintype "passive"))
      (node (ref "R222") (pin "2") (pinfunction "2_2") (pintype "passive"))
      (node (ref "T11") (pin "5") (pinfunction "B_5") (pintype "passive"))
    )
    (net (code "36") (name "Net-(T11B-C)") (class "Default")
      (node (ref "R221") (pin "2") (pinfunction "2_2") (pintype "passive"))
      (node (ref "T11") (pin "3") (pinfunction "C_3") (pintype "passive"))
    )
    (net (code "37") (name "Net-(T12A-B)") (class "Default")
      (node (ref "R205") (pin "1") (pinfunction "1_1") (pintype "passive"))
      (node (ref "R206") (pin "2") (pinfunction "2_2") (pintype "passive"))
      (node (ref "T12") (pin "2") (pinfunction "B_2") (pintype "passive"))
    )
    (net (code "38") (name "Net-(T12A-C)") (class "Default")
      (node (ref "R204") (pin "2") (pinfunction "2_2") (pintype "passive"))
      (node (ref "T12") (pin "6") (pinfunction "C_6") (pintype "passive"))
    )
    (net (code "39") (name "Net-(T12B-B)") (class "Default")
      (node (ref "R208") (pin "1") (pinfunction "1_1") (pintype "passive"))
      (node (ref "R209") (pin "2") (pinfunction "2_2") (pintype "passive"))
      (node (ref "T12") (pin "5") (pinfunction "B_5") (pintype "passive"))
    )
    (net (code "40") (name "Net-(T12B-C)") (class "Default")
      (node (ref "R207") (pin "2") (pinfunction "2_2") (pintype "passive"))
      (node (ref "T12") (pin "3") (pinfunction "C_3") (pintype "passive"))
    )
    (net (code "41") (name "Net-(T14-D)") (class "Default")
      (node (ref "R278") (pin "1") (pinfunction "1_1") (pintype "passive"))
      (node (ref "T14") (pin "3") (pinfunction "D_3") (pintype "passive"))
      (node (ref "T16") (pin "1") (pinfunction "G_1") (pintype "passive"))
    )
    (net (code "42") (name "P1V0") (class "Default")
      (node (ref "R182") (pin "2") (pinfunction "2_2") (pintype "passive"))
      (node (ref "TP13") (pin "1") (pinfunction "1_1") (pintype "bidirectional"))
    )
    (net (code "43") (name "P1V2") (class "Default")
      (node (ref "R183") (pin "2") (pinfunction "2_2") (pintype "passive"))
      (node (ref "TP14") (pin "1") (pinfunction "1_1") (pintype "bidirectional"))
    )
    (net (code "44") (name "P1V2A") (class "Default")
      (node (ref "R205") (pin "2") (pinfunction "2_2") (pintype "passive"))
      (node (ref "TP1") (pin "1") (pinfunction "1_1") (pintype "bidirectional"))
    )
    (net (code "45") (name "P1V5") (class "Default")
      (node (ref "R208") (pin "2") (pinfunction "2_2") (pintype "passive"))
      (node (ref "TP3") (pin "1") (pinfunction "1_1") (pintype "bidirectional"))
    )
    (net (code "46") (name "P1V8") (class "Default")
      (node (ref "R210") (pin "2") (pinfunction "2_2") (pintype "passive"))
      (node (ref "TP10") (pin "1") (pinfunction "1_1") (pintype "bidirectional"))
    )
    (net (code "47") (name "P2V5") (class "Default")
      (node (ref "R211") (pin "2") (pinfunction "2_2") (pintype "passive"))
      (node (ref "TP4") (pin "1") (pinfunction "1_1") (pintype "bidirectional"))
    )
    (net (code "48") (name "P3V3") (class "Default")
      (node (ref "D9") (pin "3") (pinfunction "COMAC_3") (pintype "passive"))
      (node (ref "R214") (pin "2") (pinfunction "2_2") (pintype "passive"))
      (node (ref "R262") (pin "2") (pinfunction "2_2") (pintype "passive"))
      (node (ref "R276") (pin "1") (pinfunction "1_1") (pintype "passive"))
      (node (ref "TP7") (pin "1") (pinfunction "1_1") (pintype "bidirectional"))
    )
    (net (code "49") (name "P3V3A") (class "Default")
      (node (ref "R213") (pin "2") (pinfunction "2_2") (pintype "passive"))
      (node (ref "TP6") (pin "1") (pinfunction "1_1") (pintype "bidirectional"))
    )
    (net (code "50") (name "P3V3_CPCIS") (class "Default")
      (node (ref "C53") (pin "1") (pinfunction "1_1") (pintype "passive"))
      (node (ref "D4") (pin "2") (pinfunction "A_2") (pintype "passive"))
      (node (ref "IC40") (pin "5") (pinfunction "OUT_5") (pintype "power_in"))
    )
    (net (code "51") (name "P3V3_MP") (class "Default")
      (node (ref "D4") (pin "1") (pinfunction "C_1") (pintype "passive"))
      (node (ref "R212") (pin "2") (pinfunction "2_2") (pintype "passive"))
      (node (ref "TP5") (pin "1") (pinfunction "1_1") (pintype "bidirectional"))
    )
    (net (code "52") (name "P3V6") (class "Default")
      (node (ref "R215") (pin "2") (pinfunction "2_2") (pintype "passive"))
      (node (ref "TP15") (pin "1") (pinfunction "1_1") (pintype "bidirectional"))
    )
    (net (code "53") (name "P5V0A") (class "Default")
      (node (ref "R216") (pin "2") (pinfunction "2_2") (pintype "passive"))
      (node (ref "TP16") (pin "1") (pinfunction "1_1") (pintype "bidirectional"))
    )
    (net (code "54") (name "P5V5") (class "Default")
      (node (ref "R217") (pin "2") (pinfunction "2_2") (pintype "passive"))
      (node (ref "TP8") (pin "1") (pinfunction "1_1") (pintype "bidirectional"))
    )
    (net (code "55") (name "P11V5A") (class "Default")
      (node (ref "C179") (pin "2") (pinfunction "2_2") (pintype "passive"))
      (node (ref "D6") (pin "1") (pinfunction "C_1") (pintype "passive"))
      (node (ref "IC7") (pin "5") (pinfunction "OUT_5") (pintype "power_in"))
      (node (ref "R20") (pin "2") (pinfunction "2_2") (pintype "passive"))
      (node (ref "R219") (pin "2") (pinfunction "2_2") (pintype "passive"))
      (node (ref "TP9") (pin "1") (pinfunction "1_1") (pintype "bidirectional"))
    )
    (net (code "56") (name "P12V0") (class "Default")
      (node (ref "C249") (pin "2") (pinfunction "2_2") (pintype "passive"))
      (node (ref "C268") (pin "2") (pinfunction "2_2") (pintype "passive"))
      (node (ref "IC23") (pin "2") (pinfunction "+Vin_2") (pintype "power_in"))
      (node (ref "LD1") (pin "2") (pinfunction "A_2") (pintype "passive"))
      (node (ref "LD10") (pin "2") (pinfunction "A_2") (pintype "passive"))
      (node (ref "LD12") (pin "2") (pinfunction "A_2") (pintype "passive"))
      (node (ref "LD13") (pin "2") (pinfunction "A_2") (pintype "passive"))
      (node (ref "LD9") (pin "2") (pinfunction "A_2") (pintype "passive"))
      (node (ref "R218") (pin "2") (pinfunction "2_2") (pintype "passive"))
      (node (ref "R278") (pin "2") (pinfunction "2_2") (pintype "passive"))
      (node (ref "R311") (pin "1") (pinfunction "1_1") (pintype "passive"))
      (node (ref "R312") (pin "1") (pinfunction "1_1") (pintype "passive"))
      (node (ref "R313") (pin "1") (pinfunction "1_1") (pintype "passive"))
      (node (ref "R314") (pin "1") (pinfunction "1_1") (pintype "passive"))
      (node (ref "T16") (pin "2") (pinfunction "S_2") (pintype "passive"))
      (node (ref "TP18") (pin "1") (pinfunction "1_1") (pintype "bidirectional"))
    )
    (net (code "57") (name "P12V0A") (class "Default")
      (node (ref "C245") (pin "2") (pinfunction "2_2") (pintype "passive"))
      (node (ref "C364") (pin "1") (pinfunction "1_1") (pintype "passive"))
      (node (ref "IC7") (pin "1") (pinfunction "IN_1") (pintype "input"))
      (node (ref "L45") (pin "2") (pinfunction "2_2") (pintype "passive"))
    )
    (net (code "58") (name "P12V0_CPCIS") (class "Default")
      (node (ref "C52") (pin "2") (pinfunction "2_2") (pintype "passive"))
      (node (ref "IC40") (pin "1") (pinfunction "IN_1") (pintype "input"))
      (node (ref "IC40") (pin "3") (pinfunction "EN_3") (pintype "input"))
      (node (ref "R311") (pin "2") (pinfunction "2_2") (pintype "passive"))
      (node (ref "R312") (pin "2") (pinfunction "2_2") (pintype "passive"))
      (node (ref "R313") (pin "2") (pinfunction "2_2") (pintype "passive"))
      (node (ref "R314") (pin "2") (pinfunction "2_2") (pintype "passive"))
    )
    (net (code "59") (name "unconnected-(D8B-C-Pad2)") (class "Default")
      (node (ref "D8") (pin "2") (pinfunction "C_2") (pintype "passive+no_connect"))
    )
    (net (code "60") (name "unconnected-(D9B-C-Pad2)") (class "Default")
      (node (ref "D9") (pin "2") (pinfunction "C_2") (pintype "passive+no_connect"))
    )
    (net (code "61") (name "unconnected-(IC40-BYP-Pad4)") (class "Default")
      (node (ref "IC40") (pin "4") (pinfunction "BYP_4") (pintype "passive+no_connect"))
    )
    (net (code "62") (name "unconnected-(T11A-B-Pad2)") (class "Default")
      (node (ref "T11") (pin "2") (pinfunction "B_2") (pintype "passive+no_connect"))
    )
    (net (code "63") (name "unconnected-(T11A-C-Pad6)") (class "Default")
      (node (ref "T11") (pin "6") (pinfunction "C_6") (pintype "passive+no_connect"))
    )
    (net (code "64") (name "unconnected-(T11A-E-Pad1)") (class "Default")
      (node (ref "T11") (pin "1") (pinfunction "E_1") (pintype "passive+no_connect"))
    )
  )
)
